# design.net
KiCad netlist of a schematic drawn in EasyEDA Pro
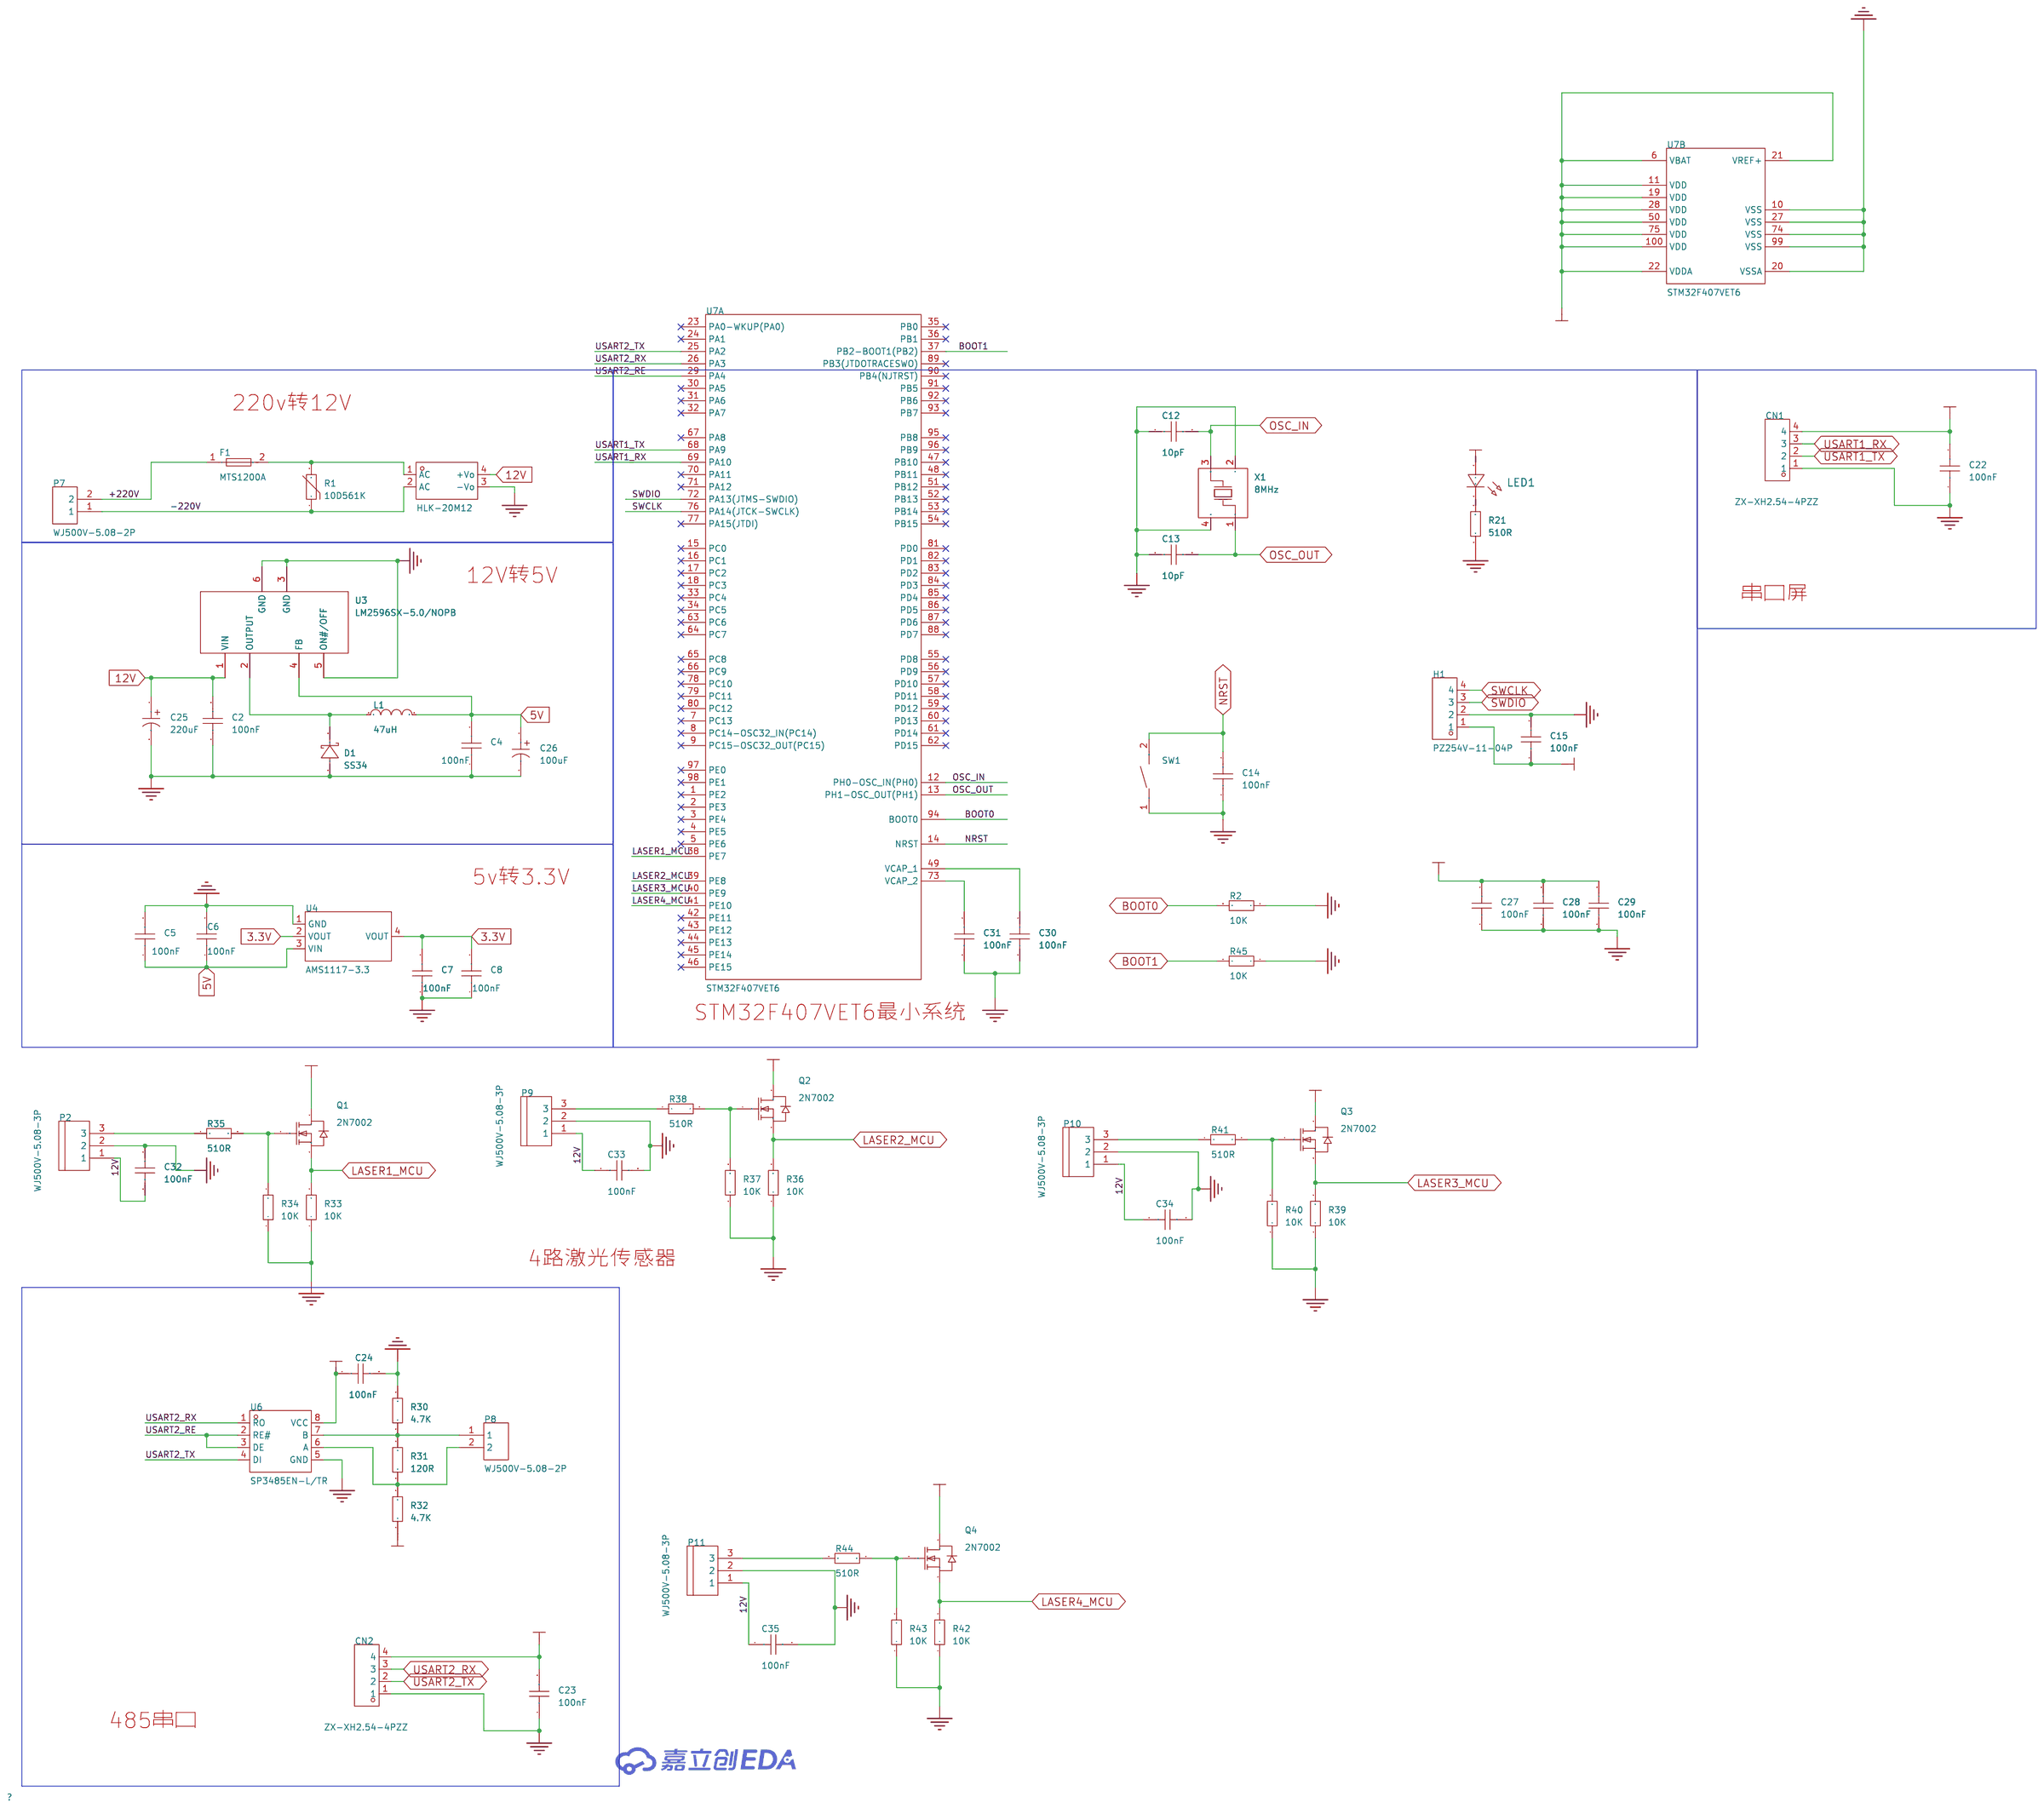
[diagram p0: schematic sheet]

(export (version "E")
  (design (tool "Eeschema 10.0.6"))
  (components
    (comp (ref "C2")
      (value "100nF")
      (footprint "easyedapro:C0603")
      (libsource (lib "easyedapro") (part "CapAcitance"))
    )
    (comp (ref "C4")
      (value "100nF")
      (footprint "easyedapro:C0603")
      (libsource (lib "easyedapro") (part "CapAcitance"))
    )
    (comp (ref "C5")
      (value "100nF")
      (footprint "easyedapro:C0603")
      (libsource (lib "easyedapro") (part "CapAcitance"))
    )
    (comp (ref "C6")
      (value "100nF")
      (footprint "easyedapro:C0603")
      (libsource (lib "easyedapro") (part "CapAcitance"))
    )
    (comp (ref "C7")
      (value "100nF")
      (footprint "easyedapro:C0603")
      (libsource (lib "easyedapro") (part "CapAcitance"))
    )
    (comp (ref "C8")
      (value "100nF")
      (footprint "easyedapro:C0603")
      (libsource (lib "easyedapro") (part "CapAcitance"))
    )
    (comp (ref "C12")
      (value "10pF")
      (footprint "easyedapro:C0603")
      (libsource (lib "easyedapro") (part "CapAcitance"))
    )
    (comp (ref "C13")
      (value "10pF")
      (footprint "easyedapro:C0603")
      (libsource (lib "easyedapro") (part "CapAcitance"))
    )
    (comp (ref "C14")
      (value "100nF")
      (footprint "easyedapro:C0603")
      (libsource (lib "easyedapro") (part "CapAcitance"))
    )
    (comp (ref "C15")
      (value "100nF")
      (footprint "easyedapro:C0603")
      (libsource (lib "easyedapro") (part "CapAcitance"))
    )
    (comp (ref "C22")
      (value "100nF")
      (footprint "easyedapro:C0603")
      (libsource (lib "easyedapro") (part "CapAcitance"))
    )
    (comp (ref "C23")
      (value "100nF")
      (footprint "easyedapro:C0603")
      (libsource (lib "easyedapro") (part "CapAcitance"))
    )
    (comp (ref "C24")
      (value "100nF")
      (footprint "easyedapro:C0603")
      (libsource (lib "easyedapro") (part "CapAcitance"))
    )
    (comp (ref "C25")
      (value "220uF")
      (footprint "easyedapro:CAP-SMD_BD8.0-L8.3-W8.3-FD")
      (description "容值:220uF;精度:±20%;额定电压:35V;纹波电流:175mA@120Hz;")
      (fields
        (field (name "Manufacturer Part") "GVT1V227M0810CNVC")
        (field (name "Manufacturer") "HRK(鸿瑞凯电子)")
      )
      (libsource (lib "easyedapro") (part "GVT1V227M0810CNVC"))
    )
    (comp (ref "C26")
      (value "100uF")
      (footprint "easyedapro:CAP-SMD_BD6.3-L6.6-W6.6-FD-1")
      (description "容值:100uF;精度:±20%;额定电压:25V;纹波电流:72mA@120Hz;")
      (fields (field (name "Manufacturer Part") "JVJ25V100M6x5") (field (name "Manufacturer") "捷而瑞"))
      (libsource (lib "easyedapro") (part "JVJ25V100M6X5"))
    )
    (comp (ref "C27")
      (value "100nF")
      (footprint "easyedapro:C0603")
      (libsource (lib "easyedapro") (part "CapAcitance"))
    )
    (comp (ref "C28")
      (value "100nF")
      (footprint "easyedapro:C0603")
      (libsource (lib "easyedapro") (part "CapAcitance"))
    )
    (comp (ref "C29")
      (value "100nF")
      (footprint "easyedapro:C0603")
      (libsource (lib "easyedapro") (part "CapAcitance"))
    )
    (comp (ref "C30")
      (value "100nF")
      (footprint "easyedapro:C0603")
      (libsource (lib "easyedapro") (part "CapAcitance"))
    )
    (comp (ref "C31")
      (value "100nF")
      (footprint "easyedapro:C0603")
      (libsource (lib "easyedapro") (part "CapAcitance"))
    )
    (comp (ref "C32")
      (value "100nF")
      (footprint "easyedapro:C0603")
      (libsource (lib "easyedapro") (part "CapAcitance"))
    )
    (comp (ref "C33")
      (value "100nF")
      (footprint "easyedapro:C0603")
      (libsource (lib "easyedapro") (part "CapAcitance"))
    )
    (comp (ref "C34")
      (value "100nF")
      (footprint "easyedapro:C0603")
      (libsource (lib "easyedapro") (part "CapAcitance"))
    )
    (comp (ref "C35")
      (value "100nF")
      (footprint "easyedapro:C0603")
      (libsource (lib "easyedapro") (part "CapAcitance"))
    )
    (comp (ref "CN1")
      (value "ZX-XH2.54-4PZZ")
      (footprint "easyedapro:CONN-TH_4P-P2.50_4PIN")
      (fields (field (name "Manufacturer") "Megastar(兆星)"))
      (libsource (lib "easyedapro") (part "ZX-XH2.54-4PZZ"))
    )
    (comp (ref "CN2")
      (value "ZX-XH2.54-4PZZ")
      (footprint "easyedapro:CONN-TH_4P-P2.50_4PIN")
      (fields (field (name "Manufacturer") "Megastar(兆星)"))
      (libsource (lib "easyedapro") (part "ZX-XH2.54-4PZZ"))
    )
    (comp (ref "D1")
      (value "SS34")
      (footprint "easyedapro:SMA_L4.3-W2.6-LS5.0-FD")
      (description "二极管配置:独立式;正向压降(Vf):550mV@3.0A;直流反向耐压(Vr):40V;平均整流电流(Io):3A;")
      (fields (field (name "Manufacturer") "宏迦橙"))
      (libsource (lib "easyedapro") (part "SS34_C7420365"))
    )
    (comp (ref "F1")
      (value "MTS1200A")
      (footprint "easyedapro:FUSE-TH_L8.4-W4.0-P5.08-D0.6")
      (description "类型:方形保险丝;额定电流:2A;")
      (fields (field (name "Manufacturer") "Reomax(瑞迈)"))
      (libsource (lib "easyedapro") (part "MTS1200A"))
    )
    (comp (ref "H1")
      (value "PZ254V-11-04P")
      (footprint "easyedapro:HDR-TH_4P-P2.54-V-M")
      (fields (field (name "Manufacturer") "XFCN(兴飞)"))
      (libsource (lib "easyedapro") (part "PZ254V-11-04P_C2691448"))
    )
    (comp (ref "L1")
      (value "47uH")
      (footprint "easyedapro:IND-SMD_L12.0-W12.0")
      (description "电感值:47uH;精度:±20%;额定电流:3.6A;")
      (fields (field (name "Manufacturer Part") "YPRH1209-470M") (field (name "Manufacturer") "YJYCOIN(益嘉源)"))
      (libsource (lib "easyedapro") (part "YPRH1209-470M"))
    )
    (comp (ref "LED1")
      (value "~")
      (footprint "easyedapro:LED_0603")
      (libsource (lib "easyedapro") (part "LED_R"))
    )
    (comp (ref "P2")
      (value "WJ500V-5.08-3P")
      (footprint "easyedapro:CONN-TH_3P-P5.00_WJ500V-5.08-3P")
      (fields (field (name "Manufacturer") "KANGNEX(康奈克斯电气)"))
      (libsource (lib "easyedapro") (part "WJ500V-5.08-3P-14-00A"))
    )
    (comp (ref "P7")
      (value "WJ500V-5.08-2P")
      (footprint "easyedapro:CONN-TH_2P-P5.00_WJ500V-5.08-2P")
      (fields (field (name "Manufacturer") "KANGNEX(康奈克斯电气)"))
      (libsource (lib "easyedapro") (part "WJ500V-5.08-2P-14-00A"))
    )
    (comp (ref "P8")
      (value "WJ500V-5.08-2P")
      (footprint "easyedapro:CONN-TH_2P-P5.00_WJ500V-5.08-2P")
      (fields (field (name "Manufacturer") "KANGNEX(康奈克斯电气)"))
      (libsource (lib "easyedapro") (part "WJ500V-5.08-2P-14-00A"))
    )
    (comp (ref "P9")
      (value "WJ500V-5.08-3P")
      (footprint "easyedapro:CONN-TH_3P-P5.00_WJ500V-5.08-3P")
      (fields (field (name "Manufacturer") "KANGNEX(康奈克斯电气)"))
      (libsource (lib "easyedapro") (part "WJ500V-5.08-3P-14-00A"))
    )
    (comp (ref "P10")
      (value "WJ500V-5.08-3P")
      (footprint "easyedapro:CONN-TH_3P-P5.00_WJ500V-5.08-3P")
      (fields (field (name "Manufacturer") "KANGNEX(康奈克斯电气)"))
      (libsource (lib "easyedapro") (part "WJ500V-5.08-3P-14-00A"))
    )
    (comp (ref "P11")
      (value "WJ500V-5.08-3P")
      (footprint "easyedapro:CONN-TH_3P-P5.00_WJ500V-5.08-3P")
      (fields (field (name "Manufacturer") "KANGNEX(康奈克斯电气)"))
      (libsource (lib "easyedapro") (part "WJ500V-5.08-3P-14-00A"))
    )
    (comp (ref "Q1")
      (value "2N7002")
      (footprint "easyedapro:SOT-23-3_L2.9-W1.3-P1.90-LS2.4-BR")
      (fields (field (name "Manufacturer") "宏嘉诚"))
      (libsource (lib "easyedapro") (part "2N7002_C7420321"))
    )
    (comp (ref "Q2")
      (value "2N7002")
      (footprint "easyedapro:SOT-23-3_L2.9-W1.3-P1.90-LS2.4-BR")
      (fields (field (name "Manufacturer") "宏嘉诚"))
      (libsource (lib "easyedapro") (part "2N7002_C7420321"))
    )
    (comp (ref "Q3")
      (value "2N7002")
      (footprint "easyedapro:SOT-23-3_L2.9-W1.3-P1.90-LS2.4-BR")
      (fields (field (name "Manufacturer") "宏嘉诚"))
      (libsource (lib "easyedapro") (part "2N7002_C7420321"))
    )
    (comp (ref "Q4")
      (value "2N7002")
      (footprint "easyedapro:SOT-23-3_L2.9-W1.3-P1.90-LS2.4-BR")
      (fields (field (name "Manufacturer") "宏嘉诚"))
      (libsource (lib "easyedapro") (part "2N7002_C7420321"))
    )
    (comp (ref "R1")
      (value "10D561K")
      (footprint "easyedapro:RES-TH_L12.5-W7.0-P7.50-D1.2-S7.00")
      (description "压敏电压:504V~616V;钳位电压:920V;最大工作电压(DC):460V;最大工作电压(AC):350V;")
      (fields (field (name "Manufacturer") "RUILON(瑞隆源)"))
      (libsource (lib "easyedapro") (part "10D561K_C233178"))
    )
    (comp (ref "R2") (value "10K") (footprint "easyedapro:R0603") (libsource (lib "easyedapro") (part "电阻")))
    (comp (ref "R21")
      (value "510R")
      (footprint "easyedapro:R0603")
      (libsource (lib "easyedapro") (part "电阻"))
    )
    (comp (ref "R30")
      (value "4.7K")
      (footprint "easyedapro:R0603")
      (libsource (lib "easyedapro") (part "电阻"))
    )
    (comp (ref "R31")
      (value "120R")
      (footprint "easyedapro:R0603")
      (libsource (lib "easyedapro") (part "电阻"))
    )
    (comp (ref "R32")
      (value "4.7K")
      (footprint "easyedapro:R0603")
      (libsource (lib "easyedapro") (part "电阻"))
    )
    (comp (ref "R33") (value "10K") (footprint "easyedapro:R0603") (libsource (lib "easyedapro") (part "电阻")))
    (comp (ref "R34") (value "10K") (footprint "easyedapro:R0603") (libsource (lib "easyedapro") (part "电阻")))
    (comp (ref "R35")
      (value "510R")
      (footprint "easyedapro:R0603")
      (libsource (lib "easyedapro") (part "电阻"))
    )
    (comp (ref "R36") (value "10K") (footprint "easyedapro:R0603") (libsource (lib "easyedapro") (part "电阻")))
    (comp (ref "R37") (value "10K") (footprint "easyedapro:R0603") (libsource (lib "easyedapro") (part "电阻")))
    (comp (ref "R38")
      (value "510R")
      (footprint "easyedapro:R0603")
      (libsource (lib "easyedapro") (part "电阻"))
    )
    (comp (ref "R39") (value "10K") (footprint "easyedapro:R0603") (libsource (lib "easyedapro") (part "电阻")))
    (comp (ref "R40") (value "10K") (footprint "easyedapro:R0603") (libsource (lib "easyedapro") (part "电阻")))
    (comp (ref "R41")
      (value "510R")
      (footprint "easyedapro:R0603")
      (libsource (lib "easyedapro") (part "电阻"))
    )
    (comp (ref "R42") (value "10K") (footprint "easyedapro:R0603") (libsource (lib "easyedapro") (part "电阻")))
    (comp (ref "R43") (value "10K") (footprint "easyedapro:R0603") (libsource (lib "easyedapro") (part "电阻")))
    (comp (ref "R44")
      (value "510R")
      (footprint "easyedapro:R0603")
      (libsource (lib "easyedapro") (part "电阻"))
    )
    (comp (ref "R45") (value "10K") (footprint "easyedapro:R0603") (libsource (lib "easyedapro") (part "电阻")))
    (comp (ref "SW1")
      (value "TS-1088-AR02016")
      (footprint "easyedapro:SW-SMD_L3.9-W3.0-P4.45")
      (fields (field (name "Manufacturer") "XUNPU(讯普)"))
      (libsource (lib "easyedapro") (part "TS-1088-AR02016"))
    )
    (comp (ref "U2")
      (value "HLK-20M12")
      (footprint "easyedapro:PWRM-TH_HLK-20MXX")
      (fields (field (name "Manufacturer") "HI-LINK(海凌科)"))
      (libsource (lib "easyedapro") (part "HLK-20M12"))
    )
    (comp (ref "U3")
      (value "LM2596SX-5.0/NOPB")
      (footprint "easyedapro:TO-263-5_L10.2-W8.9-P1.70-TL")
      (description "功能类型:降压型;输出类型:固定;工作电压:4.5V~40V;输出电压:5V;输出电流:3A;")
      (fields (field (name "Manufacturer") "TI(德州仪器)"))
      (libsource (lib "easyedapro") (part "LM2596SX-5.0/NOPB"))
    )
    (comp (ref "U4")
      (value "AMS1117-3.3")
      (footprint "easyedapro:SOT-223-3_L6.5-W3.4-P2.30-LS7.0-BR")
      (description "输出类型:固定;工作电压:16V;输出电压:3.3V;输出电流:1A;电源纹波抑制比(PSRR):72dB@(120Hz);输出极性:正极;")
      (fields (field (name "Manufacturer") "AMS"))
      (libsource (lib "easyedapro") (part "AMS1117-3.3"))
    )
    (comp (ref "U6")
      (value "SP3485EN-L/TR")
      (footprint "easyedapro:SOIC-8_L5.0-W4.0-P1.27-LS6.0-BL")
      (description "类型:收发器;数据速率:10Mbps;")
      (fields (field (name "Manufacturer") "MaxLinear(迈凌)"))
      (libsource (lib "easyedapro") (part "SP3485EN-L/TR"))
    )
    (comp (ref "U7")
      (value "STM32F407VET6")
      (footprint "easyedapro:LQFP-100_L14.0-W14.0-P0.50-LS16.0-BL")
      (description "CPU内核:ARM-M4;CPU最大主频:168MHz;应用领域:-;")
      (fields (field (name "Manufacturer") "ST(意法半导体)"))
      (libsource (lib "easyedapro") (part "STM32F407VET6"))
    )
    (comp (ref "X1")
      (value "8MHz")
      (footprint "easyedapro:CRYSTAL-SMD_4P-L3.2-W2.5-BL")
      (description "晶振类型:贴片晶振;频率:25MHz;常温频差:±10ppm;负载电容:12pF;频率稳定度:±20ppm;")
      (fields (field (name "Manufacturer Part") "X322525MOB4SI") (field (name "Manufacturer") "YXC(扬兴晶振)"))
      (libsource (lib "easyedapro") (part "X322525MOB4SI"))
    )
  )
  (nets
    (net (code "1") (name "/+220V") (class "Default")
      (node (ref "F1") (pin "1") (pinfunction "1_1") (pintype "unspecified"))
      (node (ref "P7") (pin "2") (pinfunction "2_2") (pintype "unspecified"))
    )
    (net (code "2") (name "/-220V") (class "Default")
      (node (ref "P7") (pin "1") (pinfunction "1_1") (pintype "unspecified"))
      (node (ref "R1") (pin "1") (pinfunction "1_1") (pintype "unspecified"))
      (node (ref "U2") (pin "2") (pinfunction "AC_2") (pintype "unspecified"))
    )
    (net (code "3") (name "/USART2_RE") (class "Default")
      (node (ref "U6") (pin "2") (pinfunction "RE#_2") (pintype "unspecified"))
      (node (ref "U6") (pin "3") (pinfunction "DE_3") (pintype "unspecified"))
      (node (ref "U7") (pin "29") (pinfunction "PA4_29") (pintype "bidirectional"))
    )
    (net (code "4") (name "3.3V") (class "Default")
      (node (ref "C15") (pin "1") (pinfunction "1_1") (pintype "input"))
      (node (ref "C23") (pin "2") (pinfunction "2_2") (pintype "input"))
      (node (ref "C24") (pin "1") (pinfunction "1_1") (pintype "input"))
      (node (ref "C27") (pin "2") (pinfunction "2_2") (pintype "input"))
      (node (ref "C28") (pin "2") (pinfunction "2_2") (pintype "input"))
      (node (ref "C29") (pin "2") (pinfunction "2_2") (pintype "input"))
      (node (ref "C7") (pin "2") (pinfunction "2_2") (pintype "input"))
      (node (ref "C8") (pin "2") (pinfunction "2_2") (pintype "input"))
      (node (ref "CN2") (pin "4") (pinfunction "4_4") (pintype "unspecified"))
      (node (ref "H1") (pin "1") (pinfunction "1_1") (pintype "unspecified"))
      (node (ref "LED1") (pin "2") (pinfunction "A_2") (pintype "input"))
      (node (ref "Q1") (pin "3") (pinfunction "D_3") (pintype "unspecified"))
      (node (ref "Q2") (pin "3") (pinfunction "D_3") (pintype "unspecified"))
      (node (ref "Q3") (pin "3") (pinfunction "D_3") (pintype "unspecified"))
      (node (ref "Q4") (pin "3") (pinfunction "D_3") (pintype "unspecified"))
      (node (ref "R32") (pin "1") (pinfunction "1_1") (pintype "input"))
      (node (ref "U4") (pin "2") (pinfunction "VOUT_2") (pintype "unspecified"))
      (node (ref "U4") (pin "4") (pinfunction "VOUT_4") (pintype "unspecified"))
      (node (ref "U6") (pin "8") (pinfunction "VCC_8") (pintype "unspecified"))
      (node (ref "U7") (pin "100") (pinfunction "VDD_100") (pintype "unspecified"))
      (node (ref "U7") (pin "11") (pinfunction "VDD_11") (pintype "unspecified"))
      (node (ref "U7") (pin "19") (pinfunction "VDD_19") (pintype "unspecified"))
      (node (ref "U7") (pin "21") (pinfunction "VREF+_21") (pintype "unspecified"))
      (node (ref "U7") (pin "22") (pinfunction "VDDA_22") (pintype "unspecified"))
      (node (ref "U7") (pin "28") (pinfunction "VDD_28") (pintype "unspecified"))
      (node (ref "U7") (pin "50") (pinfunction "VDD_50") (pintype "unspecified"))
      (node (ref "U7") (pin "6") (pinfunction "VBAT_6") (pintype "unspecified"))
      (node (ref "U7") (pin "75") (pinfunction "VDD_75") (pintype "unspecified"))
    )
    (net (code "5") (name "5V") (class "Default")
      (node (ref "C22") (pin "2") (pinfunction "2_2") (pintype "input"))
      (node (ref "C26") (pin "1") (pinfunction "1_1") (pintype "input"))
      (node (ref "C4") (pin "2") (pinfunction "2_2") (pintype "input"))
      (node (ref "C5") (pin "1") (pinfunction "1_1") (pintype "input"))
      (node (ref "C6") (pin "1") (pinfunction "1_1") (pintype "input"))
      (node (ref "CN1") (pin "4") (pinfunction "4_4") (pintype "unspecified"))
      (node (ref "L1") (pin "2") (pinfunction "2_2") (pintype "unspecified"))
      (node (ref "U3") (pin "4") (pinfunction "FB_4") (pintype "unspecified"))
      (node (ref "U4") (pin "3") (pinfunction "VIN_3") (pintype "unspecified"))
    )
    (net (code "6") (name "12V") (class "Default")
      (node (ref "C2") (pin "2") (pinfunction "2_2") (pintype "input"))
      (node (ref "C25") (pin "1") (pinfunction "1_1") (pintype "input"))
      (node (ref "C32") (pin "2") (pinfunction "2_2") (pintype "input"))
      (node (ref "C33") (pin "1") (pinfunction "1_1") (pintype "input"))
      (node (ref "C34") (pin "1") (pinfunction "1_1") (pintype "input"))
      (node (ref "C35") (pin "1") (pinfunction "1_1") (pintype "input"))
      (node (ref "P10") (pin "1") (pinfunction "1_1") (pintype "unspecified"))
      (node (ref "P11") (pin "1") (pinfunction "1_1") (pintype "unspecified"))
      (node (ref "P2") (pin "1") (pinfunction "1_1") (pintype "unspecified"))
      (node (ref "P9") (pin "1") (pinfunction "1_1") (pintype "unspecified"))
      (node (ref "U2") (pin "4") (pinfunction "+Vo_4") (pintype "unspecified"))
      (node (ref "U3") (pin "1") (pinfunction "VIN_1") (pintype "unspecified"))
    )
    (net (code "7") (name "BOOT0") (class "Default")
      (node (ref "R2") (pin "2") (pinfunction "2_2") (pintype "input"))
      (node (ref "U7") (pin "94") (pinfunction "BOOT0_94") (pintype "unspecified"))
    )
    (net (code "8") (name "BOOT1") (class "Default")
      (node (ref "R45") (pin "2") (pinfunction "2_2") (pintype "input"))
      (node (ref "U7") (pin "37") (pinfunction "PB2-BOOT1(PB2)_37") (pintype "bidirectional"))
    )
    (net (code "9") (name "GND") (class "Default")
      (node (ref "C12") (pin "1") (pinfunction "1_1") (pintype "input"))
      (node (ref "C13") (pin "1") (pinfunction "1_1") (pintype "input"))
      (node (ref "C14") (pin "1") (pinfunction "1_1") (pintype "input"))
      (node (ref "C15") (pin "2") (pinfunction "2_2") (pintype "input"))
      (node (ref "C2") (pin "1") (pinfunction "1_1") (pintype "input"))
      (node (ref "C22") (pin "1") (pinfunction "1_1") (pintype "input"))
      (node (ref "C23") (pin "1") (pinfunction "1_1") (pintype "input"))
      (node (ref "C24") (pin "2") (pinfunction "2_2") (pintype "input"))
      (node (ref "C25") (pin "2") (pinfunction "2_2") (pintype "input"))
      (node (ref "C26") (pin "2") (pinfunction "2_2") (pintype "input"))
      (node (ref "C27") (pin "1") (pinfunction "1_1") (pintype "input"))
      (node (ref "C28") (pin "1") (pinfunction "1_1") (pintype "input"))
      (node (ref "C29") (pin "1") (pinfunction "1_1") (pintype "input"))
      (node (ref "C30") (pin "2") (pinfunction "2_2") (pintype "input"))
      (node (ref "C31") (pin "2") (pinfunction "2_2") (pintype "input"))
      (node (ref "C32") (pin "1") (pinfunction "1_1") (pintype "input"))
      (node (ref "C33") (pin "2") (pinfunction "2_2") (pintype "input"))
      (node (ref "C34") (pin "2") (pinfunction "2_2") (pintype "input"))
      (node (ref "C35") (pin "2") (pinfunction "2_2") (pintype "input"))
      (node (ref "C4") (pin "1") (pinfunction "1_1") (pintype "input"))
      (node (ref "C5") (pin "2") (pinfunction "2_2") (pintype "input"))
      (node (ref "C6") (pin "2") (pinfunction "2_2") (pintype "input"))
      (node (ref "C7") (pin "1") (pinfunction "1_1") (pintype "input"))
      (node (ref "C8") (pin "1") (pinfunction "1_1") (pintype "input"))
      (node (ref "CN1") (pin "1") (pinfunction "1_1") (pintype "unspecified"))
      (node (ref "CN2") (pin "1") (pinfunction "1_1") (pintype "unspecified"))
      (node (ref "D1") (pin "1") (pinfunction "A_1") (pintype "unspecified"))
      (node (ref "H1") (pin "2") (pinfunction "2_2") (pintype "unspecified"))
      (node (ref "P10") (pin "2") (pinfunction "2_2") (pintype "unspecified"))
      (node (ref "P11") (pin "2") (pinfunction "2_2") (pintype "unspecified"))
      (node (ref "P2") (pin "2") (pinfunction "2_2") (pintype "unspecified"))
      (node (ref "P9") (pin "2") (pinfunction "2_2") (pintype "unspecified"))
      (node (ref "R2") (pin "1") (pinfunction "1_1") (pintype "input"))
      (node (ref "R21") (pin "1") (pinfunction "1_1") (pintype "input"))
      (node (ref "R30") (pin "2") (pinfunction "2_2") (pintype "input"))
      (node (ref "R33") (pin "1") (pinfunction "1_1") (pintype "input"))
      (node (ref "R34") (pin "1") (pinfunction "1_1") (pintype "input"))
      (node (ref "R36") (pin "1") (pinfunction "1_1") (pintype "input"))
      (node (ref "R37") (pin "1") (pinfunction "1_1") (pintype "input"))
      (node (ref "R39") (pin "1") (pinfunction "1_1") (pintype "input"))
      (node (ref "R40") (pin "1") (pinfunction "1_1") (pintype "input"))
      (node (ref "R42") (pin "1") (pinfunction "1_1") (pintype "input"))
      (node (ref "R43") (pin "1") (pinfunction "1_1") (pintype "input"))
      (node (ref "R45") (pin "1") (pinfunction "1_1") (pintype "input"))
      (node (ref "SW1") (pin "1") (pinfunction "1_1") (pintype "unspecified"))
      (node (ref "U2") (pin "3") (pinfunction "-Vo_3") (pintype "unspecified"))
      (node (ref "U3") (pin "3") (pinfunction "GND_3") (pintype "unspecified"))
      (node (ref "U3") (pin "5") (pinfunction "ON#/OFF_5") (pintype "unspecified"))
      (node (ref "U3") (pin "6") (pinfunction "GND_6") (pintype "unspecified"))
      (node (ref "U4") (pin "1") (pinfunction "GND_1") (pintype "unspecified"))
      (node (ref "U6") (pin "5") (pinfunction "GND_5") (pintype "unspecified"))
      (node (ref "U7") (pin "10") (pinfunction "VSS_10") (pintype "unspecified"))
      (node (ref "U7") (pin "20") (pinfunction "VSSA_20") (pintype "unspecified"))
      (node (ref "U7") (pin "27") (pinfunction "VSS_27") (pintype "unspecified"))
      (node (ref "U7") (pin "74") (pinfunction "VSS_74") (pintype "unspecified"))
      (node (ref "U7") (pin "99") (pinfunction "VSS_99") (pintype "unspecified"))
      (node (ref "X1") (pin "2") (pinfunction "GND_2") (pintype "unspecified"))
      (node (ref "X1") (pin "4") (pinfunction "GND_4") (pintype "unspecified"))
    )
    (net (code "10") (name "LASER1_MCU") (class "Default")
      (node (ref "Q1") (pin "2") (pinfunction "S_2") (pintype "unspecified"))
      (node (ref "R33") (pin "2") (pinfunction "2_2") (pintype "input"))
      (node (ref "U7") (pin "38") (pinfunction "PE7_38") (pintype "bidirectional"))
    )
    (net (code "11") (name "LASER2_MCU") (class "Default")
      (node (ref "Q2") (pin "2") (pinfunction "S_2") (pintype "unspecified"))
      (node (ref "R36") (pin "2") (pinfunction "2_2") (pintype "input"))
      (node (ref "U7") (pin "39") (pinfunction "PE8_39") (pintype "bidirectional"))
    )
    (net (code "12") (name "LASER3_MCU") (class "Default")
      (node (ref "Q3") (pin "2") (pinfunction "S_2") (pintype "unspecified"))
      (node (ref "R39") (pin "2") (pinfunction "2_2") (pintype "input"))
      (node (ref "U7") (pin "40") (pinfunction "PE9_40") (pintype "bidirectional"))
    )
    (net (code "13") (name "LASER4_MCU") (class "Default")
      (node (ref "Q4") (pin "2") (pinfunction "S_2") (pintype "unspecified"))
      (node (ref "R42") (pin "2") (pinfunction "2_2") (pintype "input"))
      (node (ref "U7") (pin "41") (pinfunction "PE10_41") (pintype "bidirectional"))
    )
    (net (code "14") (name "NRST") (class "Default")
      (node (ref "C14") (pin "2") (pinfunction "2_2") (pintype "input"))
      (node (ref "SW1") (pin "2") (pinfunction "2_2") (pintype "unspecified"))
      (node (ref "U7") (pin "14") (pinfunction "NRST_14") (pintype "bidirectional"))
    )
    (net (code "15") (name "Net-(D1-K)") (class "Default")
      (node (ref "D1") (pin "2") (pinfunction "K_2") (pintype "unspecified"))
      (node (ref "L1") (pin "1") (pinfunction "1_1") (pintype "unspecified"))
      (node (ref "U3") (pin "2") (pinfunction "OUTPUT_2") (pintype "unspecified"))
    )
    (net (code "16") (name "Net-(F1-Pad2)") (class "Default")
      (node (ref "F1") (pin "2") (pinfunction "2_2") (pintype "unspecified"))
      (node (ref "R1") (pin "2") (pinfunction "2_2") (pintype "unspecified"))
      (node (ref "U2") (pin "1") (pinfunction "AC_1") (pintype "unspecified"))
    )
    (net (code "17") (name "Net-(LED1-C)") (class "Default")
      (node (ref "LED1") (pin "1") (pinfunction "C_1") (pintype "input"))
      (node (ref "R21") (pin "2") (pinfunction "2_2") (pintype "input"))
    )
    (net (code "18") (name "Net-(P2-Pad3)") (class "Default")
      (node (ref "P2") (pin "3") (pinfunction "3_3") (pintype "unspecified"))
      (node (ref "R35") (pin "1") (pinfunction "1_1") (pintype "input"))
    )
    (net (code "19") (name "Net-(P9-Pad3)") (class "Default")
      (node (ref "P9") (pin "3") (pinfunction "3_3") (pintype "unspecified"))
      (node (ref "R38") (pin "1") (pinfunction "1_1") (pintype "input"))
    )
    (net (code "20") (name "Net-(P10-Pad3)") (class "Default")
      (node (ref "P10") (pin "3") (pinfunction "3_3") (pintype "unspecified"))
      (node (ref "R41") (pin "1") (pinfunction "1_1") (pintype "input"))
    )
    (net (code "21") (name "Net-(P11-Pad3)") (class "Default")
      (node (ref "P11") (pin "3") (pinfunction "3_3") (pintype "unspecified"))
      (node (ref "R44") (pin "1") (pinfunction "1_1") (pintype "input"))
    )
    (net (code "22") (name "Net-(Q1-G)") (class "Default")
      (node (ref "Q1") (pin "1") (pinfunction "G_1") (pintype "unspecified"))
      (node (ref "R34") (pin "2") (pinfunction "2_2") (pintype "input"))
      (node (ref "R35") (pin "2") (pinfunction "2_2") (pintype "input"))
    )
    (net (code "23") (name "Net-(Q2-G)") (class "Default")
      (node (ref "Q2") (pin "1") (pinfunction "G_1") (pintype "unspecified"))
      (node (ref "R37") (pin "2") (pinfunction "2_2") (pintype "input"))
      (node (ref "R38") (pin "2") (pinfunction "2_2") (pintype "input"))
    )
    (net (code "24") (name "Net-(Q3-G)") (class "Default")
      (node (ref "Q3") (pin "1") (pinfunction "G_1") (pintype "unspecified"))
      (node (ref "R40") (pin "2") (pinfunction "2_2") (pintype "input"))
      (node (ref "R41") (pin "2") (pinfunction "2_2") (pintype "input"))
    )
    (net (code "25") (name "Net-(Q4-G)") (class "Default")
      (node (ref "Q4") (pin "1") (pinfunction "G_1") (pintype "unspecified"))
      (node (ref "R43") (pin "2") (pinfunction "2_2") (pintype "input"))
      (node (ref "R44") (pin "2") (pinfunction "2_2") (pintype "input"))
    )
    (net (code "26") (name "Net-(U6-A)") (class "Default")
      (node (ref "P8") (pin "2") (pinfunction "2_2") (pintype "unspecified"))
      (node (ref "R31") (pin "1") (pinfunction "1_1") (pintype "input"))
      (node (ref "R32") (pin "2") (pinfunction "2_2") (pintype "input"))
      (node (ref "U6") (pin "6") (pinfunction "A_6") (pintype "unspecified"))
    )
    (net (code "27") (name "Net-(U6-B)") (class "Default")
      (node (ref "P8") (pin "1") (pinfunction "1_1") (pintype "unspecified"))
      (node (ref "R30") (pin "1") (pinfunction "1_1") (pintype "input"))
      (node (ref "R31") (pin "2") (pinfunction "2_2") (pintype "input"))
      (node (ref "U6") (pin "7") (pinfunction "B_7") (pintype "unspecified"))
    )
    (net (code "28") (name "Net-(U7A-VCAP_1)") (class "Default")
      (node (ref "C30") (pin "1") (pinfunction "1_1") (pintype "input"))
      (node (ref "U7") (pin "49") (pinfunction "VCAP_1_49") (pintype "unspecified"))
    )
    (net (code "29") (name "Net-(U7A-VCAP_2)") (class "Default")
      (node (ref "C31") (pin "1") (pinfunction "1_1") (pintype "input"))
      (node (ref "U7") (pin "73") (pinfunction "VCAP_2_73") (pintype "unspecified"))
    )
    (net (code "30") (name "OSC_IN") (class "Default")
      (node (ref "C12") (pin "2") (pinfunction "2_2") (pintype "input"))
      (node (ref "U7") (pin "12") (pinfunction "PH0-OSC_IN(PH0)_12") (pintype "bidirectional"))
      (node (ref "X1") (pin "3") (pinfunction "OSC2_3") (pintype "unspecified"))
    )
    (net (code "31") (name "OSC_OUT") (class "Default")
      (node (ref "C13") (pin "2") (pinfunction "2_2") (pintype "input"))
      (node (ref "U7") (pin "13") (pinfunction "PH1-OSC_OUT(PH1)_13") (pintype "bidirectional"))
      (node (ref "X1") (pin "1") (pinfunction "OSC1_1") (pintype "unspecified"))
    )
    (net (code "32") (name "SWCLK") (class "Default")
      (node (ref "H1") (pin "4") (pinfunction "4_4") (pintype "unspecified"))
      (node (ref "U7") (pin "76") (pinfunction "PA14(JTCK-SWCLK)_76") (pintype "bidirectional"))
    )
    (net (code "33") (name "SWDIO") (class "Default")
      (node (ref "H1") (pin "3") (pinfunction "3_3") (pintype "unspecified"))
      (node (ref "U7") (pin "72") (pinfunction "PA13(JTMS-SWDIO)_72") (pintype "bidirectional"))
    )
    (net (code "34") (name "USART1_RX") (class "Default")
      (node (ref "CN1") (pin "3") (pinfunction "3_3") (pintype "unspecified"))
      (node (ref "U7") (pin "69") (pinfunction "PA10_69") (pintype "bidirectional"))
    )
    (net (code "35") (name "USART1_TX") (class "Default")
      (node (ref "CN1") (pin "2") (pinfunction "2_2") (pintype "unspecified"))
      (node (ref "U7") (pin "68") (pinfunction "PA9_68") (pintype "bidirectional"))
    )
    (net (code "36") (name "USART2_RX") (class "Default")
      (node (ref "CN2") (pin "3") (pinfunction "3_3") (pintype "unspecified"))
      (node (ref "U6") (pin "1") (pinfunction "RO_1") (pintype "unspecified"))
      (node (ref "U7") (pin "26") (pinfunction "PA3_26") (pintype "bidirectional"))
    )
    (net (code "37") (name "USART2_TX") (class "Default")
      (node (ref "CN2") (pin "2") (pinfunction "2_2") (pintype "unspecified"))
      (node (ref "U6") (pin "4") (pinfunction "DI_4") (pintype "unspecified"))
      (node (ref "U7") (pin "25") (pinfunction "PA2_25") (pintype "bidirectional"))
    )
    (net (code "38") (name "unconnected-(U7A-PA0-WKUP(PA0)-Pad23)") (class "Default")
      (node (ref "U7") (pin "23") (pinfunction "PA0-WKUP(PA0)_23") (pintype "bidirectional+no_connect"))
    )
    (net (code "39") (name "unconnected-(U7A-PA1-Pad24)") (class "Default")
      (node (ref "U7") (pin "24") (pinfunction "PA1_24") (pintype "bidirectional+no_connect"))
    )
    (net (code "40") (name "unconnected-(U7A-PA5-Pad30)") (class "Default")
      (node (ref "U7") (pin "30") (pinfunction "PA5_30") (pintype "bidirectional+no_connect"))
    )
    (net (code "41") (name "unconnected-(U7A-PA6-Pad31)") (class "Default")
      (node (ref "U7") (pin "31") (pinfunction "PA6_31") (pintype "bidirectional+no_connect"))
    )
    (net (code "42") (name "unconnected-(U7A-PA7-Pad32)") (class "Default")
      (node (ref "U7") (pin "32") (pinfunction "PA7_32") (pintype "bidirectional+no_connect"))
    )
    (net (code "43") (name "unconnected-(U7A-PA8-Pad67)") (class "Default")
      (node (ref "U7") (pin "67") (pinfunction "PA8_67") (pintype "bidirectional+no_connect"))
    )
    (net (code "44") (name "unconnected-(U7A-PA11-Pad70)") (class "Default")
      (node (ref "U7") (pin "70") (pinfunction "PA11_70") (pintype "bidirectional+no_connect"))
    )
    (net (code "45") (name "unconnected-(U7A-PA12-Pad71)") (class "Default")
      (node (ref "U7") (pin "71") (pinfunction "PA12_71") (pintype "bidirectional+no_connect"))
    )
    (net (code "46") (name "unconnected-(U7A-PA15(JTDI)-Pad77)") (class "Default")
      (node (ref "U7") (pin "77") (pinfunction "PA15(JTDI)_77") (pintype "bidirectional+no_connect"))
    )
    (net (code "47") (name "unconnected-(U7A-PB0-Pad35)") (class "Default")
      (node (ref "U7") (pin "35") (pinfunction "PB0_35") (pintype "bidirectional+no_connect"))
    )
    (net (code "48") (name "unconnected-(U7A-PB1-Pad36)") (class "Default")
      (node (ref "U7") (pin "36") (pinfunction "PB1_36") (pintype "bidirectional+no_connect"))
    )
    (net (code "49") (name "unconnected-(U7A-PB3(JTDOTRACESWO)-Pad89)") (class "Default")
      (node (ref "U7") (pin "89") (pinfunction "PB3(JTDOTRACESWO)_89") (pintype "bidirectional+no_connect"))
    )
    (net (code "50") (name "unconnected-(U7A-PB4(NJTRST)-Pad90)") (class "Default")
      (node (ref "U7") (pin "90") (pinfunction "PB4(NJTRST)_90") (pintype "bidirectional+no_connect"))
    )
    (net (code "51") (name "unconnected-(U7A-PB5-Pad91)") (class "Default")
      (node (ref "U7") (pin "91") (pinfunction "PB5_91") (pintype "bidirectional+no_connect"))
    )
    (net (code "52") (name "unconnected-(U7A-PB6-Pad92)") (class "Default")
      (node (ref "U7") (pin "92") (pinfunction "PB6_92") (pintype "bidirectional+no_connect"))
    )
    (net (code "53") (name "unconnected-(U7A-PB7-Pad93)") (class "Default")
      (node (ref "U7") (pin "93") (pinfunction "PB7_93") (pintype "bidirectional+no_connect"))
    )
    (net (code "54") (name "unconnected-(U7A-PB8-Pad95)") (class "Default")
      (node (ref "U7") (pin "95") (pinfunction "PB8_95") (pintype "bidirectional+no_connect"))
    )
    (net (code "55") (name "unconnected-(U7A-PB9-Pad96)") (class "Default")
      (node (ref "U7") (pin "96") (pinfunction "PB9_96") (pintype "bidirectional+no_connect"))
    )
    (net (code "56") (name "unconnected-(U7A-PB10-Pad47)") (class "Default")
      (node (ref "U7") (pin "47") (pinfunction "PB10_47") (pintype "bidirectional+no_connect"))
    )
    (net (code "57") (name "unconnected-(U7A-PB11-Pad48)") (class "Default")
      (node (ref "U7") (pin "48") (pinfunction "PB11_48") (pintype "bidirectional+no_connect"))
    )
    (net (code "58") (name "unconnected-(U7A-PB12-Pad51)") (class "Default")
      (node (ref "U7") (pin "51") (pinfunction "PB12_51") (pintype "bidirectional+no_connect"))
    )
    (net (code "59") (name "unconnected-(U7A-PB13-Pad52)") (class "Default")
      (node (ref "U7") (pin "52") (pinfunction "PB13_52") (pintype "bidirectional+no_connect"))
    )
    (net (code "60") (name "unconnected-(U7A-PB14-Pad53)") (class "Default")
      (node (ref "U7") (pin "53") (pinfunction "PB14_53") (pintype "bidirectional+no_connect"))
    )
    (net (code "61") (name "unconnected-(U7A-PB15-Pad54)") (class "Default")
      (node (ref "U7") (pin "54") (pinfunction "PB15_54") (pintype "bidirectional+no_connect"))
    )
    (net (code "62") (name "unconnected-(U7A-PC0-Pad15)") (class "Default")
      (node (ref "U7") (pin "15") (pinfunction "PC0_15") (pintype "bidirectional+no_connect"))
    )
    (net (code "63") (name "unconnected-(U7A-PC1-Pad16)") (class "Default")
      (node (ref "U7") (pin "16") (pinfunction "PC1_16") (pintype "bidirectional+no_connect"))
    )
    (net (code "64") (name "unconnected-(U7A-PC2-Pad17)") (class "Default")
      (node (ref "U7") (pin "17") (pinfunction "PC2_17") (pintype "bidirectional+no_connect"))
    )
    (net (code "65") (name "unconnected-(U7A-PC3-Pad18)") (class "Default")
      (node (ref "U7") (pin "18") (pinfunction "PC3_18") (pintype "bidirectional+no_connect"))
    )
    (net (code "66") (name "unconnected-(U7A-PC4-Pad33)") (class "Default")
      (node (ref "U7") (pin "33") (pinfunction "PC4_33") (pintype "bidirectional+no_connect"))
    )
    (net (code "67") (name "unconnected-(U7A-PC5-Pad34)") (class "Default")
      (node (ref "U7") (pin "34") (pinfunction "PC5_34") (pintype "bidirectional+no_connect"))
    )
    (net (code "68") (name "unconnected-(U7A-PC6-Pad63)") (class "Default")
      (node (ref "U7") (pin "63") (pinfunction "PC6_63") (pintype "bidirectional+no_connect"))
    )
    (net (code "69") (name "unconnected-(U7A-PC7-Pad64)") (class "Default")
      (node (ref "U7") (pin "64") (pinfunction "PC7_64") (pintype "bidirectional+no_connect"))
    )
    (net (code "70") (name "unconnected-(U7A-PC8-Pad65)") (class "Default")
      (node (ref "U7") (pin "65") (pinfunction "PC8_65") (pintype "bidirectional+no_connect"))
    )
    (net (code "71") (name "unconnected-(U7A-PC9-Pad66)") (class "Default")
      (node (ref "U7") (pin "66") (pinfunction "PC9_66") (pintype "bidirectional+no_connect"))
    )
    (net (code "72") (name "unconnected-(U7A-PC10-Pad78)") (class "Default")
      (node (ref "U7") (pin "78") (pinfunction "PC10_78") (pintype "bidirectional+no_connect"))
    )
    (net (code "73") (name "unconnected-(U7A-PC11-Pad79)") (class "Default")
      (node (ref "U7") (pin "79") (pinfunction "PC11_79") (pintype "bidirectional+no_connect"))
    )
    (net (code "74") (name "unconnected-(U7A-PC12-Pad80)") (class "Default")
      (node (ref "U7") (pin "80") (pinfunction "PC12_80") (pintype "bidirectional+no_connect"))
    )
    (net (code "75") (name "unconnected-(U7A-PC13-Pad7)") (class "Default")
      (node (ref "U7") (pin "7") (pinfunction "PC13_7") (pintype "bidirectional+no_connect"))
    )
    (net (code "76") (name "unconnected-(U7A-PC14-OSC32_IN(PC14)-Pad8)") (class "Default")
      (node (ref "U7") (pin "8") (pinfunction "PC14-OSC32_IN(PC14)_8") (pintype "bidirectional+no_connect"))
    )
    (net (code "77") (name "unconnected-(U7A-PC15-OSC32_OUT(PC15)-Pad9)") (class "Default")
      (node (ref "U7") (pin "9") (pinfunction "PC15-OSC32_OUT(PC15)_9") (pintype "bidirectional+no_connect"))
    )
    (net (code "78") (name "unconnected-(U7A-PD0-Pad81)") (class "Default")
      (node (ref "U7") (pin "81") (pinfunction "PD0_81") (pintype "bidirectional+no_connect"))
    )
    (net (code "79") (name "unconnected-(U7A-PD1-Pad82)") (class "Default")
      (node (ref "U7") (pin "82") (pinfunction "PD1_82") (pintype "bidirectional+no_connect"))
    )
    (net (code "80") (name "unconnected-(U7A-PD2-Pad83)") (class "Default")
      (node (ref "U7") (pin "83") (pinfunction "PD2_83") (pintype "bidirectional+no_connect"))
    )
    (net (code "81") (name "unconnected-(U7A-PD3-Pad84)") (class "Default")
      (node (ref "U7") (pin "84") (pinfunction "PD3_84") (pintype "bidirectional+no_connect"))
    )
    (net (code "82") (name "unconnected-(U7A-PD4-Pad85)") (class "Default")
      (node (ref "U7") (pin "85") (pinfunction "PD4_85") (pintype "bidirectional+no_connect"))
    )
    (net (code "83") (name "unconnected-(U7A-PD5-Pad86)") (class "Default")
      (node (ref "U7") (pin "86") (pinfunction "PD5_86") (pintype "bidirectional+no_connect"))
    )
    (net (code "84") (name "unconnected-(U7A-PD6-Pad87)") (class "Default")
      (node (ref "U7") (pin "87") (pinfunction "PD6_87") (pintype "bidirectional+no_connect"))
    )
    (net (code "85") (name "unconnected-(U7A-PD7-Pad88)") (class "Default")
      (node (ref "U7") (pin "88") (pinfunction "PD7_88") (pintype "bidirectional+no_connect"))
    )
    (net (code "86") (name "unconnected-(U7A-PD8-Pad55)") (class "Default")
      (node (ref "U7") (pin "55") (pinfunction "PD8_55") (pintype "bidirectional+no_connect"))
    )
    (net (code "87") (name "unconnected-(U7A-PD9-Pad56)") (class "Default")
      (node (ref "U7") (pin "56") (pinfunction "PD9_56") (pintype "bidirectional+no_connect"))
    )
    (net (code "88") (name "unconnected-(U7A-PD10-Pad57)") (class "Default")
      (node (ref "U7") (pin "57") (pinfunction "PD10_57") (pintype "bidirectional+no_connect"))
    )
    (net (code "89") (name "unconnected-(U7A-PD11-Pad58)") (class "Default")
      (node (ref "U7") (pin "58") (pinfunction "PD11_58") (pintype "bidirectional+no_connect"))
    )
    (net (code "90") (name "unconnected-(U7A-PD12-Pad59)") (class "Default")
      (node (ref "U7") (pin "59") (pinfunction "PD12_59") (pintype "bidirectional+no_connect"))
    )
    (net (code "91") (name "unconnected-(U7A-PD13-Pad60)") (class "Default")
      (node (ref "U7") (pin "60") (pinfunction "PD13_60") (pintype "bidirectional+no_connect"))
    )
    (net (code "92") (name "unconnected-(U7A-PD14-Pad61)") (class "Default")
      (node (ref "U7") (pin "61") (pinfunction "PD14_61") (pintype "bidirectional+no_connect"))
    )
    (net (code "93") (name "unconnected-(U7A-PD15-Pad62)") (class "Default")
      (node (ref "U7") (pin "62") (pinfunction "PD15_62") (pintype "bidirectional+no_connect"))
    )
    (net (code "94") (name "unconnected-(U7A-PE0-Pad97)") (class "Default")
      (node (ref "U7") (pin "97") (pinfunction "PE0_97") (pintype "bidirectional+no_connect"))
    )
    (net (code "95") (name "unconnected-(U7A-PE1-Pad98)") (class "Default")
      (node (ref "U7") (pin "98") (pinfunction "PE1_98") (pintype "bidirectional+no_connect"))
    )
    (net (code "96") (name "unconnected-(U7A-PE2-Pad1)") (class "Default")
      (node (ref "U7") (pin "1") (pinfunction "PE2_1") (pintype "bidirectional+no_connect"))
    )
    (net (code "97") (name "unconnected-(U7A-PE3-Pad2)") (class "Default")
      (node (ref "U7") (pin "2") (pinfunction "PE3_2") (pintype "bidirectional+no_connect"))
    )
    (net (code "98") (name "unconnected-(U7A-PE4-Pad3)") (class "Default")
      (node (ref "U7") (pin "3") (pinfunction "PE4_3") (pintype "bidirectional+no_connect"))
    )
    (net (code "99") (name "unconnected-(U7A-PE5-Pad4)") (class "Default")
      (node (ref "U7") (pin "4") (pinfunction "PE5_4") (pintype "bidirectional+no_connect"))
    )
    (net (code "100") (name "unconnected-(U7A-PE6-Pad5)") (class "Default")
      (node (ref "U7") (pin "5") (pinfunction "PE6_5") (pintype "bidirectional+no_connect"))
    )
    (net (code "101") (name "unconnected-(U7A-PE11-Pad42)") (class "Default")
      (node (ref "U7") (pin "42") (pinfunction "PE11_42") (pintype "bidirectional+no_connect"))
    )
    (net (code "102") (name "unconnected-(U7A-PE12-Pad43)") (class "Default")
      (node (ref "U7") (pin "43") (pinfunction "PE12_43") (pintype "bidirectional+no_connect"))
    )
    (net (code "103") (name "unconnected-(U7A-PE13-Pad44)") (class "Default")
      (node (ref "U7") (pin "44") (pinfunction "PE13_44") (pintype "bidirectional+no_connect"))
    )
    (net (code "104") (name "unconnected-(U7A-PE14-Pad45)") (class "Default")
      (node (ref "U7") (pin "45") (pinfunction "PE14_45") (pintype "bidirectional+no_connect"))
    )
    (net (code "105") (name "unconnected-(U7A-PE15-Pad46)") (class "Default")
      (node (ref "U7") (pin "46") (pinfunction "PE15_46") (pintype "bidirectional+no_connect"))
    )
  )
)
